# Register_8B.net
KiCad netlist of a schematic drawn in Altium Designer
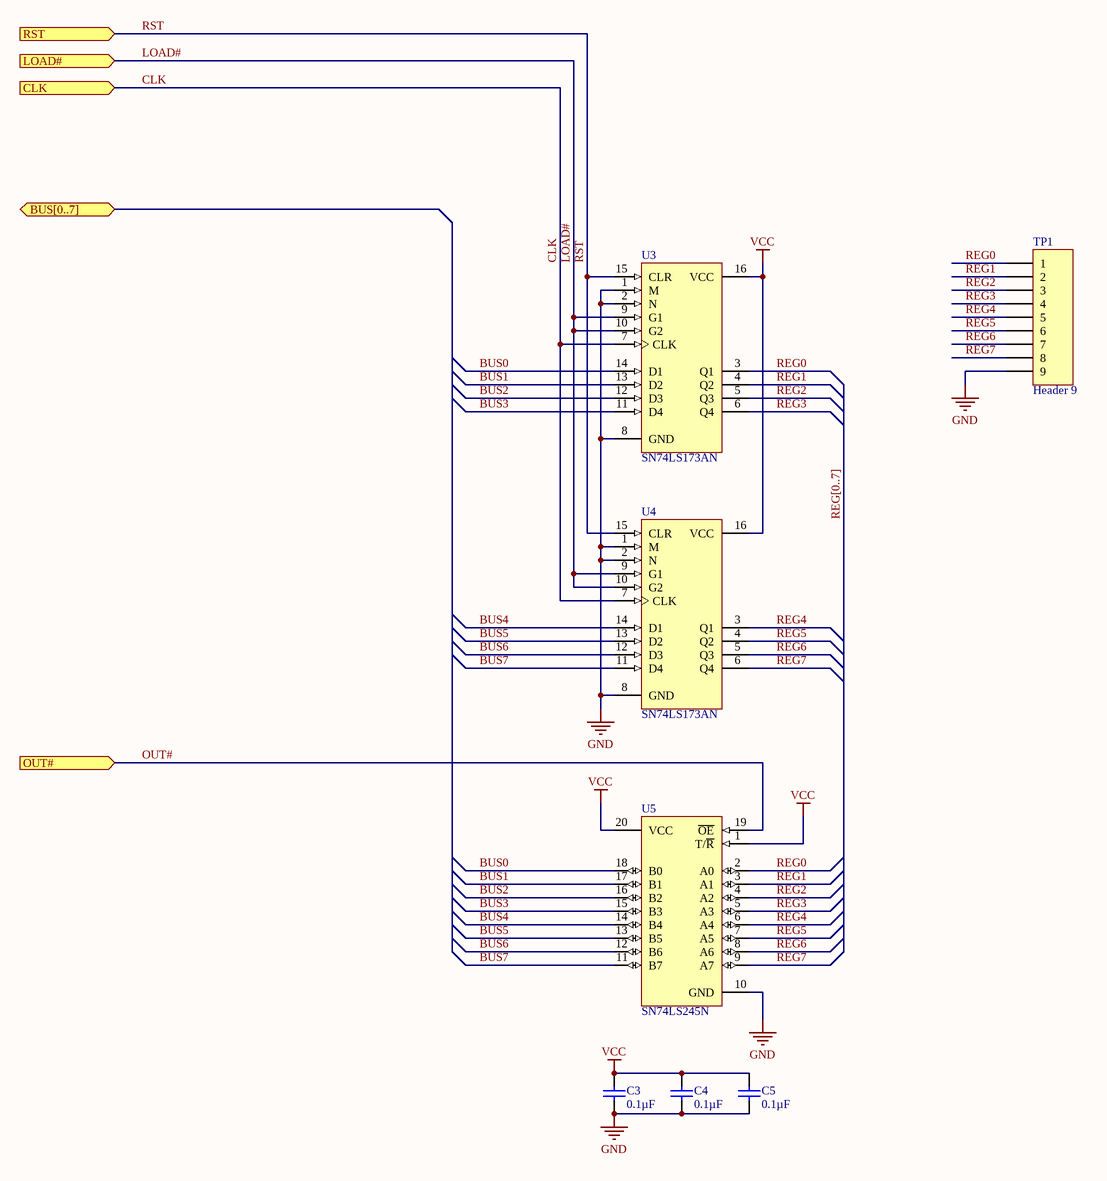
[diagram p0: Register_8B.SchDoc]

(export (version "E")
  (design (tool "Eeschema 10.0.6"))
  (components
    (comp (ref "C3")
      (value "K104K15X7RF5TL2")
      (footprint "VISH-K104K15X7RF5TL2")
      (description "Ceramic Capacitor, 100 nF, +/- 10%, 50 V, -55 to 125 degC, 2-Pin THD, RoHS, Tape and Reel")
      (fields
        (field (name "MANUFACTURER") "Vishay")
        (field (name "TOLERANCE") "±10%")
        (field (name "CAPACITANCE") "0.1µF")
      )
      (libsource (lib "Altium Content Vault") (part "CAP-NP-2"))
    )
    (comp (ref "C4")
      (value "K104K15X7RF5TL2")
      (footprint "VISH-K104K15X7RF5TL2")
      (description "Ceramic Capacitor, 100 nF, +/- 10%, 50 V, -55 to 125 degC, 2-Pin THD, RoHS, Tape and Reel")
      (fields
        (field (name "MANUFACTURER") "Vishay")
        (field (name "TOLERANCE") "±10%")
        (field (name "CAPACITANCE") "0.1µF")
      )
      (libsource (lib "Altium Content Vault") (part "CAP-NP-2"))
    )
    (comp (ref "C5")
      (value "K104K15X7RF5TL2")
      (footprint "VISH-K104K15X7RF5TL2")
      (description "Ceramic Capacitor, 100 nF, +/- 10%, 50 V, -55 to 125 degC, 2-Pin THD, RoHS, Tape and Reel")
      (fields
        (field (name "MANUFACTURER") "Vishay")
        (field (name "TOLERANCE") "±10%")
        (field (name "CAPACITANCE") "0.1µF")
      )
      (libsource (lib "Altium Content Vault") (part "CAP-NP-2"))
    )
    (comp (ref "TP1")
      (value "Header 9")
      (footprint "HDR1X9")
      (description "Header, 9-Pin")
      (fields (field (name "PUBLISHER") "Altium Limited"))
      (libsource (lib "Miscellaneous Connectors") (part "Header 9"))
    )
    (comp (ref "U3")
      (value "SN74LS173AN")
      (footprint "N016D")
      (description "4-Bit D-Type Register with 3-State Outputs")
      (fields (field (name "PUBLISHER") "Altium Limited"))
      (libsource (lib "TI Logic Flip-Flop") (part "SN74LS173AN"))
    )
    (comp (ref "U4")
      (value "SN74LS173AN")
      (footprint "N016D")
      (description "4-Bit D-Type Register with 3-State Outputs")
      (fields (field (name "PUBLISHER") "Altium Limited"))
      (libsource (lib "TI Logic Flip-Flop") (part "SN74LS173AN"))
    )
    (comp (ref "U5")
      (value "SN74LS245N")
      (footprint "N020")
      (description "Octal Bus Transceiver with 3-State Outputs")
      (fields (field (name "PUBLISHER") "Altium Limited"))
      (libsource (lib "TI Interface 8-Bit Line Transceiver") (part "SN74LS245N"))
    )
  )
  (nets
    (net (code "1") (name "/BUS0") (class "Default")
      (node (ref "U3") (pin "14") (pinfunction "D1_14") (pintype "input"))
      (node (ref "U5") (pin "18") (pinfunction "B0_18") (pintype "bidirectional"))
    )
    (net (code "2") (name "/BUS1") (class "Default")
      (node (ref "U3") (pin "13") (pinfunction "D2_13") (pintype "input"))
      (node (ref "U5") (pin "17") (pinfunction "B1_17") (pintype "bidirectional"))
    )
    (net (code "3") (name "/BUS2") (class "Default")
      (node (ref "U3") (pin "12") (pinfunction "D3_12") (pintype "input"))
      (node (ref "U5") (pin "16") (pinfunction "B2_16") (pintype "bidirectional"))
    )
    (net (code "4") (name "/BUS3") (class "Default")
      (node (ref "U3") (pin "11") (pinfunction "D4_11") (pintype "input"))
      (node (ref "U5") (pin "15") (pinfunction "B3_15") (pintype "bidirectional"))
    )
    (net (code "5") (name "/BUS4") (class "Default")
      (node (ref "U4") (pin "14") (pinfunction "D1_14") (pintype "input"))
      (node (ref "U5") (pin "14") (pinfunction "B4_14") (pintype "bidirectional"))
    )
    (net (code "6") (name "/BUS5") (class "Default")
      (node (ref "U4") (pin "13") (pinfunction "D2_13") (pintype "input"))
      (node (ref "U5") (pin "13") (pinfunction "B5_13") (pintype "bidirectional"))
    )
    (net (code "7") (name "/BUS6") (class "Default")
      (node (ref "U4") (pin "12") (pinfunction "D3_12") (pintype "input"))
      (node (ref "U5") (pin "12") (pinfunction "B6_12") (pintype "bidirectional"))
    )
    (net (code "8") (name "/BUS7") (class "Default")
      (node (ref "U4") (pin "11") (pinfunction "D4_11") (pintype "input"))
      (node (ref "U5") (pin "11") (pinfunction "B7_11") (pintype "bidirectional"))
    )
    (net (code "10") (name "/CLK") (class "Default")
      (node (ref "U3") (pin "7") (pinfunction "CLK_7") (pintype "input"))
      (node (ref "U4") (pin "7") (pinfunction "CLK_7") (pintype "input"))
    )
    (net (code "11") (name "/LOAD#") (class "Default")
      (node (ref "U3") (pin "10") (pinfunction "G2_10") (pintype "input"))
      (node (ref "U3") (pin "9") (pinfunction "G1_9") (pintype "input"))
      (node (ref "U4") (pin "10") (pinfunction "G2_10") (pintype "input"))
      (node (ref "U4") (pin "9") (pinfunction "G1_9") (pintype "input"))
    )
    (net (code "12") (name "/OUT#") (class "Default")
      (node (ref "U5") (pin "19") (pinfunction "~{OE}_19") (pintype "input"))
    )
    (net (code "13") (name "/REG0") (class "Default")
      (node (ref "TP1") (pin "1") (pinfunction "1_1") (pintype "passive"))
      (node (ref "U3") (pin "3") (pinfunction "Q1_3") (pintype "tri_state"))
      (node (ref "U5") (pin "2") (pinfunction "A0_2") (pintype "bidirectional"))
    )
    (net (code "14") (name "/REG1") (class "Default")
      (node (ref "TP1") (pin "2") (pinfunction "2_2") (pintype "passive"))
      (node (ref "U3") (pin "4") (pinfunction "Q2_4") (pintype "tri_state"))
      (node (ref "U5") (pin "3") (pinfunction "A1_3") (pintype "bidirectional"))
    )
    (net (code "15") (name "/REG2") (class "Default")
      (node (ref "TP1") (pin "3") (pinfunction "3_3") (pintype "passive"))
      (node (ref "U3") (pin "5") (pinfunction "Q3_5") (pintype "tri_state"))
      (node (ref "U5") (pin "4") (pinfunction "A2_4") (pintype "bidirectional"))
    )
    (net (code "16") (name "/REG3") (class "Default")
      (node (ref "TP1") (pin "4") (pinfunction "4_4") (pintype "passive"))
      (node (ref "U3") (pin "6") (pinfunction "Q4_6") (pintype "tri_state"))
      (node (ref "U5") (pin "5") (pinfunction "A3_5") (pintype "bidirectional"))
    )
    (net (code "17") (name "/REG4") (class "Default")
      (node (ref "TP1") (pin "5") (pinfunction "5_5") (pintype "passive"))
      (node (ref "U4") (pin "3") (pinfunction "Q1_3") (pintype "tri_state"))
      (node (ref "U5") (pin "6") (pinfunction "A4_6") (pintype "bidirectional"))
    )
    (net (code "18") (name "/REG5") (class "Default")
      (node (ref "TP1") (pin "6") (pinfunction "6_6") (pintype "passive"))
      (node (ref "U4") (pin "4") (pinfunction "Q2_4") (pintype "tri_state"))
      (node (ref "U5") (pin "7") (pinfunction "A5_7") (pintype "bidirectional"))
    )
    (net (code "19") (name "/REG6") (class "Default")
      (node (ref "TP1") (pin "7") (pinfunction "7_7") (pintype "passive"))
      (node (ref "U4") (pin "5") (pinfunction "Q3_5") (pintype "tri_state"))
      (node (ref "U5") (pin "8") (pinfunction "A6_8") (pintype "bidirectional"))
    )
    (net (code "20") (name "/REG7") (class "Default")
      (node (ref "TP1") (pin "8") (pinfunction "8_8") (pintype "passive"))
      (node (ref "U4") (pin "6") (pinfunction "Q4_6") (pintype "tri_state"))
      (node (ref "U5") (pin "9") (pinfunction "A7_9") (pintype "bidirectional"))
    )
    (net (code "22") (name "/RST") (class "Default")
      (node (ref "U3") (pin "15") (pinfunction "CLR_15") (pintype "input"))
      (node (ref "U4") (pin "15") (pinfunction "CLR_15") (pintype "input"))
    )
    (net (code "23") (name "GND") (class "Default")
      (node (ref "C3") (pin "2") (pinfunction "2_2") (pintype "passive"))
      (node (ref "C4") (pin "2") (pinfunction "2_2") (pintype "passive"))
      (node (ref "C5") (pin "2") (pinfunction "2_2") (pintype "passive"))
      (node (ref "TP1") (pin "9") (pinfunction "9_9") (pintype "passive"))
      (node (ref "U3") (pin "1") (pinfunction "M_1") (pintype "input"))
      (node (ref "U3") (pin "2") (pinfunction "N_2") (pintype "input"))
      (node (ref "U3") (pin "8") (pinfunction "GND_8") (pintype "power_in"))
      (node (ref "U4") (pin "1") (pinfunction "M_1") (pintype "input"))
      (node (ref "U4") (pin "2") (pinfunction "N_2") (pintype "input"))
      (node (ref "U4") (pin "8") (pinfunction "GND_8") (pintype "power_in"))
      (node (ref "U5") (pin "10") (pinfunction "GND_10") (pintype "power_in"))
    )
    (net (code "24") (name "VCC") (class "Default")
      (node (ref "C3") (pin "1") (pinfunction "1_1") (pintype "passive"))
      (node (ref "C4") (pin "1") (pinfunction "1_1") (pintype "passive"))
      (node (ref "C5") (pin "1") (pinfunction "1_1") (pintype "passive"))
      (node (ref "U3") (pin "16") (pinfunction "VCC_16") (pintype "power_in"))
      (node (ref "U4") (pin "16") (pinfunction "VCC_16") (pintype "power_in"))
      (node (ref "U5") (pin "1") (pinfunction "T/~{R}_1") (pintype "input"))
      (node (ref "U5") (pin "20") (pinfunction "VCC_20") (pintype "power_in"))
    )
  )
)
